# thighPCB.net
KiCad netlist of a schematic drawn in EasyEDA Pro
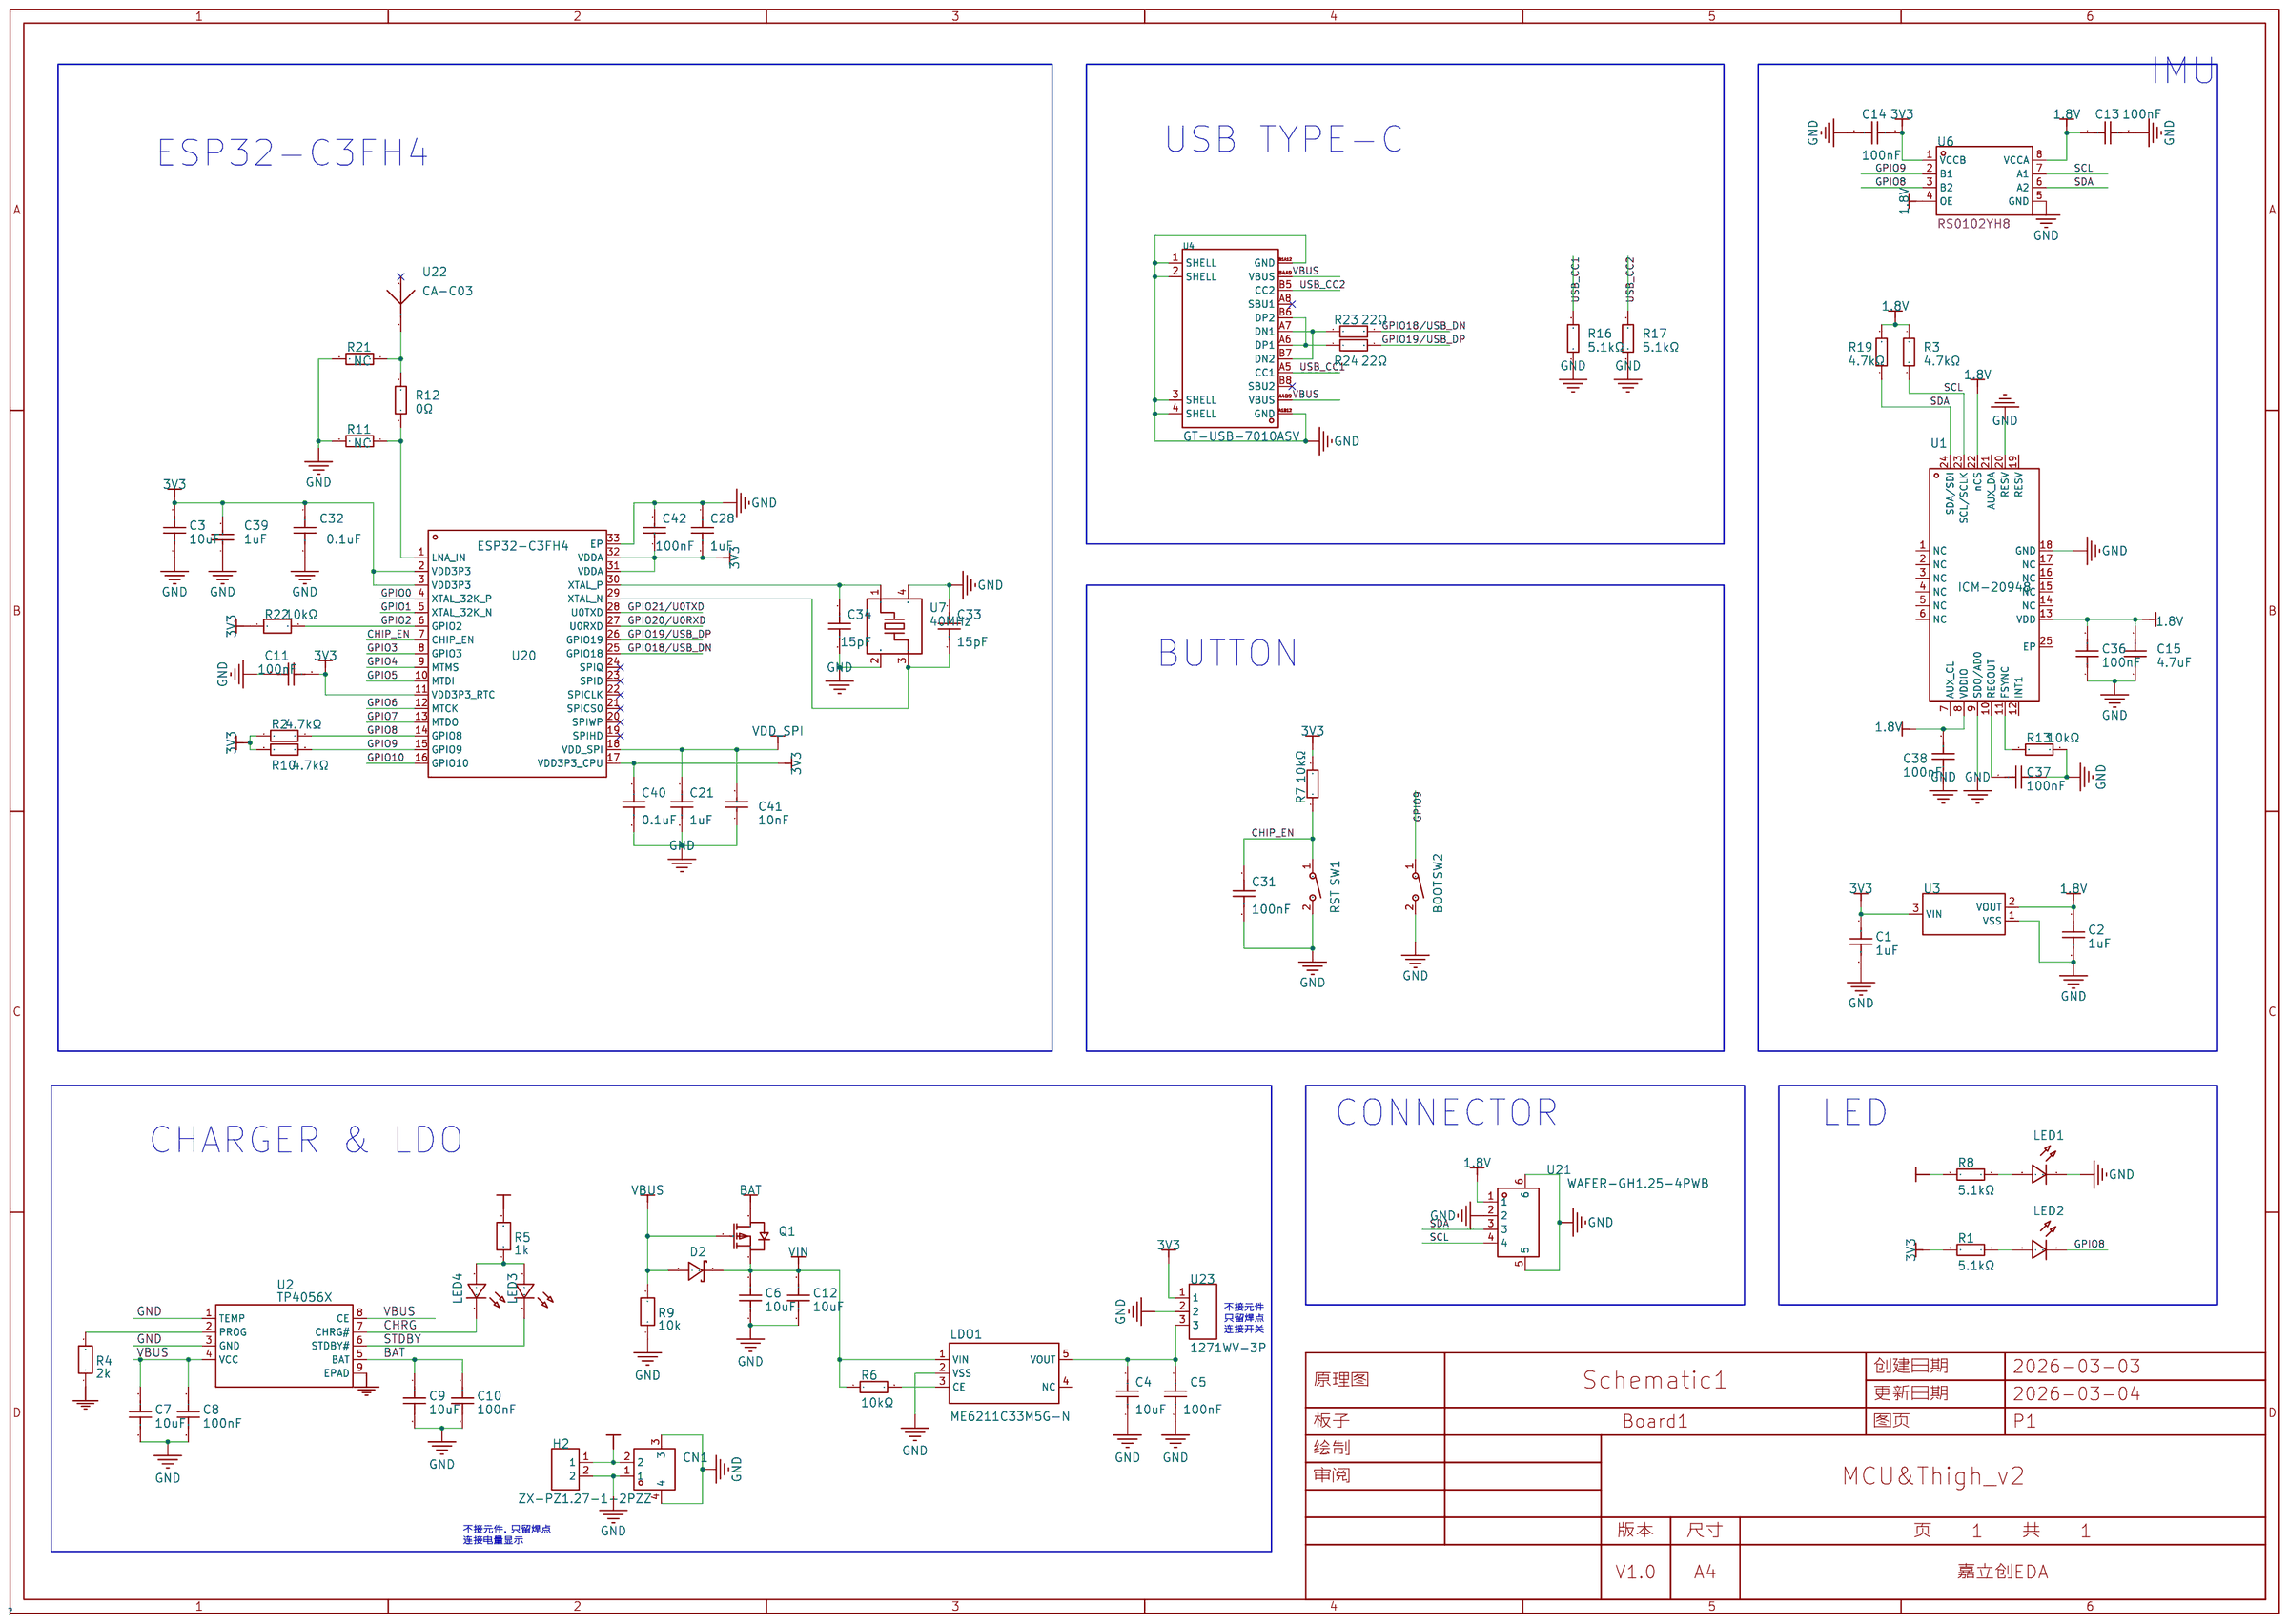
[diagram p0: schematic sheet]

(export (version "E")
  (design (tool "Eeschema 10.0.6"))
  (components
    (comp (ref "C1")
      (value "1uF")
      (footprint "easyedapro:C0603")
      (libsource (lib "easyedapro") (part "Capacitance"))
    )
    (comp (ref "C2")
      (value "1uF")
      (footprint "easyedapro:C0603")
      (libsource (lib "easyedapro") (part "Capacitance"))
    )
    (comp (ref "C3")
      (value "10uF")
      (footprint "easyedapro:C0402")
      (fields
        (field (name "Manufacturer Part") "CL05A106MP5NUNC")
        (field (name "Manufacturer") "SAMSUNG(三星)")
      )
      (libsource (lib "easyedapro") (part "CL05A106MP5NUNC_C315248"))
    )
    (comp (ref "C4")
      (value "10uF")
      (fields
        (field (name "Manufacturer Part") "CL10A106KP8NNNC")
        (field (name "Manufacturer") "SAMSUNG(三星)")
      )
      (libsource (lib "easyedapro") (part "capacitance"))
    )
    (comp (ref "C5")
      (value "100nF")
      (fields
        (field (name "Manufacturer Part") "CGA0603X7R104K500JT")
        (field (name "Manufacturer") "HRE(芯声)")
      )
      (libsource (lib "easyedapro") (part "capacitance"))
    )
    (comp (ref "C6")
      (value "10uF")
      (footprint "easyedapro:C0603")
      (libsource (lib "easyedapro") (part "Capacitance"))
    )
    (comp (ref "C7")
      (value "10uF")
      (footprint "easyedapro:C0603")
      (libsource (lib "easyedapro") (part "Capacitance"))
    )
    (comp (ref "C8")
      (value "100nF")
      (footprint "easyedapro:C0603")
      (libsource (lib "easyedapro") (part "Capacitance"))
    )
    (comp (ref "C9")
      (value "10uF")
      (footprint "easyedapro:C0603")
      (libsource (lib "easyedapro") (part "Capacitance"))
    )
    (comp (ref "C10")
      (value "100nF")
      (footprint "easyedapro:C0603")
      (libsource (lib "easyedapro") (part "Capacitance"))
    )
    (comp (ref "C11")
      (value "100nF")
      (footprint "easyedapro:C0201")
      (fields
        (field (name "Manufacturer Part") "GRM033Z71A104KE14D")
        (field (name "Manufacturer") "muRata(村田)")
      )
      (libsource (lib "easyedapro") (part "GRM033Z71A104KE14D"))
    )
    (comp (ref "C12")
      (value "10uF")
      (footprint "easyedapro:C0603")
      (libsource (lib "easyedapro") (part "Capacitance"))
    )
    (comp (ref "C13")
      (value "100nF")
      (footprint "easyedapro:C0201")
      (description "容值:100nF;精度:±10%;额定电压:10V;材质(温度系数):X7R;")
      (fields
        (field (name "Manufacturer Part") "GRM033Z71A104KE14D")
        (field (name "Manufacturer") "muRata(村田)")
      )
      (libsource (lib "easyedapro") (part "GRM033Z71A104KE14D"))
    )
    (comp (ref "C14")
      (value "100nF")
      (footprint "easyedapro:C0201")
      (description "容值:100nF;精度:±10%;额定电压:10V;材质(温度系数):X7R;")
      (fields
        (field (name "Manufacturer Part") "GRM033Z71A104KE14D")
        (field (name "Manufacturer") "muRata(村田)")
      )
      (libsource (lib "easyedapro") (part "GRM033Z71A104KE14D"))
    )
    (comp (ref "C15")
      (value "4.7uF")
      (footprint "easyedapro:C0603")
      (description "容值:100nF;精度:±10%;额定电压:16V;温度系数:X5R;")
      (fields
        (field (name "Manufacturer Part") "CL03A104KO3NNNC")
        (field (name "Manufacturer") "SAMSUNG(三星)")
      )
      (libsource (lib "easyedapro") (part "Capacitance"))
    )
    (comp (ref "C21")
      (value "1uF")
      (footprint "easyedapro:C0201")
      (fields
        (field (name "Manufacturer Part") "GRM033C81A105ME05D")
        (field (name "Manufacturer") "muRata(村田)")
      )
      (libsource (lib "easyedapro") (part "GRM033C81A105ME05D"))
    )
    (comp (ref "C28")
      (value "1uF")
      (footprint "easyedapro:C0201")
      (fields
        (field (name "Manufacturer Part") "GRM033C81A105ME05D")
        (field (name "Manufacturer") "muRata(村田)")
      )
      (libsource (lib "easyedapro") (part "GRM033C81A105ME05D"))
    )
    (comp (ref "C31")
      (value "100nF")
      (footprint "easyedapro:C0201")
      (fields
        (field (name "Manufacturer Part") "GRM033Z71A104KE14D")
        (field (name "Manufacturer") "muRata(村田)")
      )
      (libsource (lib "easyedapro") (part "GRM033Z71A104KE14D"))
    )
    (comp (ref "C32")
      (value "0.1uF")
      (footprint "easyedapro:C0201")
      (fields
        (field (name "Manufacturer Part") "GRM033Z71A104KE14D")
        (field (name "Manufacturer") "muRata(村田)")
      )
      (libsource (lib "easyedapro") (part "GRM033Z71A104KE14D"))
    )
    (comp (ref "C33")
      (value "15pF")
      (footprint "easyedapro:C0201")
      (fields
        (field (name "Manufacturer Part") "GRM0335C1H150FA01D")
        (field (name "Manufacturer") "muRata(村田)")
      )
      (libsource (lib "easyedapro") (part "GRM0335C1H150FA01D"))
    )
    (comp (ref "C34")
      (value "15pF")
      (footprint "easyedapro:C0201")
      (fields
        (field (name "Manufacturer Part") "GRM0335C1H150FA01D")
        (field (name "Manufacturer") "muRata(村田)")
      )
      (libsource (lib "easyedapro") (part "GRM0335C1H150FA01D"))
    )
    (comp (ref "C36")
      (value "100nF")
      (footprint "easyedapro:C0603")
      (fields
        (field (name "Manufacturer Part") "CL03A104KO3NNNC")
        (field (name "Manufacturer") "SAMSUNG(三星)")
      )
      (libsource (lib "easyedapro") (part "Capacitance"))
    )
    (comp (ref "C37")
      (value "100nF")
      (footprint "easyedapro:C0603")
      (fields
        (field (name "Manufacturer Part") "CL03A104KO3NNNC")
        (field (name "Manufacturer") "SAMSUNG(三星)")
      )
      (libsource (lib "easyedapro") (part "Capacitance"))
    )
    (comp (ref "C38")
      (value "100nF")
      (footprint "easyedapro:C0603")
      (fields
        (field (name "Manufacturer Part") "CL03A104KO3NNNC")
        (field (name "Manufacturer") "SAMSUNG(三星)")
      )
      (libsource (lib "easyedapro") (part "Capacitance"))
    )
    (comp (ref "C39")
      (value "1uF")
      (footprint "easyedapro:C0201")
      (fields
        (field (name "Manufacturer Part") "GRM033R61A105ME44D")
        (field (name "Manufacturer") "muRata(村田)")
      )
      (libsource (lib "easyedapro") (part "GRM033R61A105ME44D"))
    )
    (comp (ref "C40")
      (value "0.1uF")
      (footprint "easyedapro:C0201")
      (fields
        (field (name "Manufacturer Part") "GRM033C81A105ME05D")
        (field (name "Manufacturer") "muRata(村田)")
      )
      (libsource (lib "easyedapro") (part "GRM033C81A105ME05D"))
    )
    (comp (ref "C41")
      (value "10nF")
      (footprint "easyedapro:C0201")
      (fields
        (field (name "Manufacturer Part") "GRM033R71A103KA01D")
        (field (name "Manufacturer") "muRata(村田)")
      )
      (libsource (lib "easyedapro") (part "GRM033R71A103KA01D"))
    )
    (comp (ref "C42")
      (value "100nF")
      (footprint "easyedapro:C0201")
      (fields
        (field (name "Manufacturer Part") "GRM033R61E104KE14D")
        (field (name "Manufacturer") "muRata(村田)")
      )
      (libsource (lib "easyedapro") (part "GRM033R61E104KE14D"))
    )
    (comp (ref "CN1")
      (value "WAFER-GH1.25-2PWB")
      (footprint "easyedapro:CONN-TH_2P-P1.25_XUNPU_WAFER-GH1.25-2PWB")
      (fields (field (name "Manufacturer") "XUNPU(讯普)"))
      (libsource (lib "easyedapro") (part "WAFER-GH1.25-2PWB"))
    )
    (comp (ref "D2")
      (value "1N5819HW-7-F")
      (footprint "easyedapro:SOD-123_L2.7-W1.6-LS3.7-RD")
      (description "二极管配置:1个独立式;正向压降(Vf):450mV@1A;直流反向耐压(Vr):40V;整流电流:1A;")
      (fields (field (name "Manufacturer") "DIODES(美台)"))
      (libsource (lib "easyedapro") (part "1N5819HW-7-F"))
    )
    (comp (ref "H2")
      (value "ZX-PZ1.27-1-2PZZ")
      (footprint "easyedapro:HDR-TH_2P-P1.27-V-M-2")
      (fields (field (name "Manufacturer") "Megastar(兆星)"))
      (libsource (lib "easyedapro") (part "ZX-PZ1.27-1-2PZZ"))
    )
    (comp (ref "LDO1")
      (value "ME6211C33M5G-N")
      (footprint "easyedapro:SOT-23-5_L3.0-W1.7-P0.95-LS2.8-BL")
      (fields (field (name "Manufacturer") "MICRONE(南京微盟)"))
      (libsource (lib "easyedapro") (part "ME6211C33M5G-N"))
    )
    (comp (ref "LED1")
      (value "~")
      (footprint "easyedapro:LED_0402")
      (libsource (lib "easyedapro") (part "LED_R"))
    )
    (comp (ref "LED2")
      (value "~")
      (footprint "easyedapro:LED_0402")
      (libsource (lib "easyedapro") (part "LED_R"))
    )
    (comp (ref "LED3")
      (value "~")
      (footprint "easyedapro:LED_0603")
      (libsource (lib "easyedapro") (part "LED_G"))
    )
    (comp (ref "LED4")
      (value "~")
      (footprint "easyedapro:LED_0402")
      (libsource (lib "easyedapro") (part "LED_R"))
    )
    (comp (ref "Q1")
      (value "HL6042")
      (footprint "easyedapro:SOT-23-3_L2.9-W1.4-P1.90-LS2.5-BR")
      (fields (field (name "Manufacturer") "R+O(宏嘉诚)"))
      (libsource (lib "easyedapro") (part "HL6042"))
    )
    (comp (ref "R1")
      (value "5.1kΩ")
      (footprint "easyedapro:R0201")
      (description "阻值:5.1kΩ;精度:±1%;功率:50mW;")
      (fields (field (name "Manufacturer Part") "RC-01W5101FT") (field (name "Manufacturer") "FH(风华)"))
      (libsource (lib "easyedapro") (part "RC-01W5101FT"))
    )
    (comp (ref "R2")
      (value "4.7kΩ")
      (footprint "easyedapro:R0201")
      (description "电阻类型:厚膜电阻;阻值:10kΩ;精度:±1%;功率:50mW;")
      (fields (field (name "Manufacturer Part") "RC0201FR-0710KL") (field (name "Manufacturer") "YAGEO(国巨)"))
      (libsource (lib "easyedapro") (part "RC0201FR-0710KL"))
    )
    (comp (ref "R3")
      (value "4.7kΩ")
      (footprint "easyedapro:R0201")
      (description "电阻类型:厚膜电阻;阻值:10kΩ;精度:±1%;功率:50mW;")
      (fields (field (name "Manufacturer Part") "RC0201FR-0710KL") (field (name "Manufacturer") "YAGEO(国巨)"))
      (libsource (lib "easyedapro") (part "RC0201FR-0710KL"))
    )
    (comp (ref "R4")
      (value "2k")
      (footprint "easyedapro:R0603")
      (fields (field (name "Contributor") "LCEDA_Lib"))
      (libsource (lib "easyedapro") (part "2k"))
    )
    (comp (ref "R5")
      (value "1k")
      (footprint "easyedapro:R0603")
      (fields (field (name "Contributor") "LCEDA_Lib"))
      (libsource (lib "easyedapro") (part "1k"))
    )
    (comp (ref "R6")
      (value "10kΩ")
      (fields (field (name "Manufacturer Part") "FRC0603J103TS") (field (name "Manufacturer") "FOJAN(富捷)"))
      (libsource (lib "easyedapro") (part "电阻"))
    )
    (comp (ref "R7")
      (value "10kΩ")
      (footprint "easyedapro:R0201")
      (fields (field (name "Manufacturer Part") "RC0201FR-0710KL") (field (name "Manufacturer") "YAGEO(国巨)"))
      (libsource (lib "easyedapro") (part "RC0201FR-0710KL"))
    )
    (comp (ref "R8")
      (value "5.1kΩ")
      (footprint "easyedapro:R0201")
      (fields (field (name "Manufacturer Part") "RC-01W5101FT") (field (name "Manufacturer") "FH(风华)"))
      (libsource (lib "easyedapro") (part "RC-01W5101FT"))
    )
    (comp (ref "R9")
      (value "10k")
      (footprint "easyedapro:R0603")
      (fields (field (name "Contributor") "LCEDA_Lib"))
      (libsource (lib "easyedapro") (part "1k"))
    )
    (comp (ref "R10")
      (value "4.7kΩ")
      (footprint "easyedapro:R0201")
      (description "电阻类型:厚膜电阻;阻值:10kΩ;精度:±1%;功率:50mW;")
      (fields (field (name "Manufacturer Part") "RC0201FR-0710KL") (field (name "Manufacturer") "YAGEO(国巨)"))
      (libsource (lib "easyedapro") (part "RC0201FR-0710KL"))
    )
    (comp (ref "R11")
      (value "NC")
      (footprint "easyedapro:R0201")
      (fields (field (name "Manufacturer Part") "RC0201JR-070RL") (field (name "Manufacturer") "YAGEO(国巨)"))
      (libsource (lib "easyedapro") (part "RC0201JR-070RL"))
    )
    (comp (ref "R12")
      (value "0Ω")
      (footprint "easyedapro:R0201")
      (fields (field (name "Manufacturer Part") "RC0201JR-070RL") (field (name "Manufacturer") "YAGEO(国巨)"))
      (libsource (lib "easyedapro") (part "RC0201JR-070RL"))
    )
    (comp (ref "R13")
      (value "10kΩ")
      (footprint "easyedapro:R0201")
      (description "电阻类型:厚膜电阻;阻值:10kΩ;精度:±1%;功率:50mW;")
      (fields (field (name "Manufacturer Part") "RC0201FR-0710KL") (field (name "Manufacturer") "YAGEO(国巨)"))
      (libsource (lib "easyedapro") (part "RC0201FR-0710KL"))
    )
    (comp (ref "R16")
      (value "5.1kΩ")
      (footprint "easyedapro:R0201")
      (fields (field (name "Manufacturer Part") "RC-01W5101FT") (field (name "Manufacturer") "FH(风华)"))
      (libsource (lib "easyedapro") (part "RC-01W5101FT"))
    )
    (comp (ref "R17")
      (value "5.1kΩ")
      (footprint "easyedapro:R0201")
      (fields (field (name "Manufacturer Part") "RC-01W5101FT") (field (name "Manufacturer") "FH(风华)"))
      (libsource (lib "easyedapro") (part "RC-01W5101FT"))
    )
    (comp (ref "R19")
      (value "4.7kΩ")
      (footprint "easyedapro:R0201")
      (description "电阻类型:厚膜电阻;阻值:10kΩ;精度:±1%;功率:50mW;")
      (fields (field (name "Manufacturer Part") "RC0201FR-0710KL") (field (name "Manufacturer") "YAGEO(国巨)"))
      (libsource (lib "easyedapro") (part "RC0201FR-0710KL"))
    )
    (comp (ref "R21")
      (value "NC")
      (footprint "easyedapro:R0201")
      (fields (field (name "Manufacturer Part") "RC0201JR-070RL") (field (name "Manufacturer") "YAGEO(国巨)"))
      (libsource (lib "easyedapro") (part "RC0201JR-070RL"))
    )
    (comp (ref "R22")
      (value "10kΩ")
      (footprint "easyedapro:R0201")
      (fields (field (name "Manufacturer Part") "FRC0201J103 TS") (field (name "Manufacturer") "FOJAN(富捷)"))
      (libsource (lib "easyedapro") (part "FRC0201J103 TS"))
    )
    (comp (ref "R23")
      (value "22Ω")
      (footprint "easyedapro:R0201")
      (fields (field (name "Manufacturer Part") "RC0201FR-0722RL") (field (name "Manufacturer") "YAGEO(国巨)"))
      (libsource (lib "easyedapro") (part "RC0201FR-0722RL"))
    )
    (comp (ref "R24")
      (value "22Ω")
      (footprint "easyedapro:R0201")
      (fields (field (name "Manufacturer Part") "RC0201FR-0722RL") (field (name "Manufacturer") "YAGEO(国巨)"))
      (libsource (lib "easyedapro") (part "RC0201FR-0722RL"))
    )
    (comp (ref "SW1")
      (value "RST")
      (footprint "easyedapro:SW-SMD_L4.0-W2.9-LS5.0")
      (fields
        (field (name "Manufacturer Part") "TS-1185-C-B-B-A")
        (field (name "Manufacturer") "XKB Connectivity(中国星坤)")
      )
      (libsource (lib "easyedapro") (part "TS-1185-C-B-B-A"))
    )
    (comp (ref "SW2")
      (value "BOOT")
      (footprint "easyedapro:SW-SMD_L4.0-W2.9-LS5.0")
      (fields
        (field (name "Manufacturer Part") "TS-1185-C-B-B-A")
        (field (name "Manufacturer") "XKB Connectivity(中国星坤)")
      )
      (libsource (lib "easyedapro") (part "TS-1185-C-B-B-A"))
    )
    (comp (ref "U1")
      (value "ICM-20948")
      (footprint "easyedapro:QFN-24_L3.0-W3.0-P0.40-BL-EP")
      (fields (field (name "Manufacturer") "TDK InvenSense(应美盛)"))
      (libsource (lib "easyedapro") (part "ICM-20948"))
    )
    (comp (ref "U2")
      (value "TP4056X")
      (footprint "easyedapro:SOP-8_L4.9-W3.9-P1.27-LS6.0-BL-EP")
      (fields
        (field (name "Manufacturer") "Nanjing Extension Microelectronics")
        (field (name "Contributor") "LCSC")
      )
      (libsource (lib "easyedapro") (part "TP4056X"))
    )
    (comp (ref "U3")
      (value "ME6211A18M3G-N")
      (footprint "easyedapro:SOT-23-3_L3.0-W1.7-P0.95-LS2.9-BR")
      (fields (field (name "Manufacturer") "MICRONE(南京微盟)"))
      (libsource (lib "easyedapro") (part "ME6211A18M3G-N"))
    )
    (comp (ref "U4")
      (value "GT-USB-7010ASV")
      (footprint "easyedapro:USB-C-SMD_G-SWITCH_GT-USB-7010ASV")
      (fields (field (name "Manufacturer") "G-Switch(品赞)"))
      (libsource (lib "easyedapro") (part "GT-USB-7010ASV"))
    )
    (comp (ref "U6")
      (value "RS0102YH8")
      (footprint "easyedapro:SOT-23-8_L3.0-W1.7-P0.65-LS2.8-BL")
      (fields (field (name "Manufacturer Part") "RS0102YH8") (field (name "Manufacturer") "RUNIC(润石)"))
      (libsource (lib "easyedapro") (part "RS0102YH8"))
    )
    (comp (ref "U7")
      (value "40MHz")
      (footprint "easyedapro:CRYSTAL-SMD_4P-L2.0-W1.6-BL")
      (fields (field (name "Manufacturer Part") "TAXM40M4ZHBCDT2T") (field (name "Manufacturer") "YJX(雅晶鑫)"))
      (libsource (lib "easyedapro") (part "TAXM40M4ZHBCDT2T"))
    )
    (comp (ref "U20")
      (value "ESP32-C3FH4")
      (fields (field (name "Manufacturer") "ESPRESSIF(乐鑫)"))
      (libsource (lib "easyedapro") (part "ESP32-C3FH4"))
    )
    (comp (ref "U21")
      (value "WAFER-GH1.25-4PWB")
      (footprint "easyedapro:CONN-SMD_4P-P1.25_XUNPU_WAFER-GH1.25-4PWB")
      (fields (field (name "Manufacturer") "XUNPU(讯普)"))
      (libsource (lib "easyedapro") (part "WAFER-GH1.25-4PWB"))
    )
    (comp (ref "U22")
      (value "CA-C03")
      (footprint "easyedapro:ANT-SMD_CA-C03")
      (libsource (lib "easyedapro") (part "CA-C03_C9900042552"))
    )
    (comp (ref "U23")
      (value "1271WV-3P")
      (footprint "easyedapro:HDR-TH_3P-P1.27-V-M")
      (fields (field (name "Manufacturer") "HanElectricity(瀚源)"))
      (libsource (lib "easyedapro") (part "1271WV-3P"))
    )
  )
  (nets
    (net (code "1") (name "/CHIP_EN") (class "Default")
      (node (ref "C31") (pin "1") (pinfunction "1_1") (pintype "input"))
      (node (ref "R7") (pin "1") (pinfunction "1_1") (pintype "input"))
      (node (ref "SW1") (pin "1") (pinfunction "1_1") (pintype "input"))
      (node (ref "U20") (pin "7") (pinfunction "CHIP_EN_7") (pintype "input"))
    )
    (net (code "2") (name "/CHRG") (class "Default")
      (node (ref "LED4") (pin "1") (pinfunction "C_1") (pintype "input"))
      (node (ref "U2") (pin "7") (pinfunction "CHRG#_7") (pintype "unspecified"))
    )
    (net (code "3") (name "/GPIO0") (class "Default")
      (node (ref "U20") (pin "4") (pinfunction "XTAL_32K_P_4") (pintype "input"))
    )
    (net (code "4") (name "/GPIO1") (class "Default")
      (node (ref "U20") (pin "5") (pinfunction "XTAL_32K_N_5") (pintype "input"))
    )
    (net (code "5") (name "/GPIO2") (class "Default")
      (node (ref "R22") (pin "2") (pinfunction "2_2") (pintype "unspecified"))
      (node (ref "U20") (pin "6") (pinfunction "GPIO2_6") (pintype "input"))
    )
    (net (code "6") (name "/GPIO3") (class "Default")
      (node (ref "U20") (pin "8") (pinfunction "GPIO3_8") (pintype "input"))
    )
    (net (code "7") (name "/GPIO4") (class "Default")
      (node (ref "U20") (pin "9") (pinfunction "MTMS_9") (pintype "input"))
    )
    (net (code "8") (name "/GPIO5") (class "Default")
      (node (ref "U20") (pin "10") (pinfunction "MTDI_10") (pintype "input"))
    )
    (net (code "9") (name "/GPIO6") (class "Default")
      (node (ref "U20") (pin "12") (pinfunction "MTCK_12") (pintype "input"))
    )
    (net (code "10") (name "/GPIO7") (class "Default")
      (node (ref "U20") (pin "13") (pinfunction "MTDO_13") (pintype "input"))
    )
    (net (code "11") (name "/GPIO8") (class "Default")
      (node (ref "LED2") (pin "1") (pinfunction "C_1") (pintype "input"))
      (node (ref "R2") (pin "2") (pinfunction "2_2") (pintype "input"))
      (node (ref "U20") (pin "14") (pinfunction "GPIO8_14") (pintype "input"))
      (node (ref "U6") (pin "3") (pinfunction "B2_3") (pintype "unspecified"))
    )
    (net (code "12") (name "/GPIO9") (class "Default")
      (node (ref "R10") (pin "2") (pinfunction "2_2") (pintype "input"))
      (node (ref "SW2") (pin "1") (pinfunction "1_1") (pintype "input"))
      (node (ref "U20") (pin "15") (pinfunction "GPIO9_15") (pintype "input"))
      (node (ref "U6") (pin "2") (pinfunction "B1_2") (pintype "unspecified"))
    )
    (net (code "13") (name "/GPIO10") (class "Default")
      (node (ref "U20") (pin "16") (pinfunction "GPIO10_16") (pintype "input"))
    )
    (net (code "14") (name "/GPIO18{slash}USB_DN") (class "Default")
      (node (ref "R23") (pin "2") (pinfunction "2_2") (pintype "unspecified"))
      (node (ref "U20") (pin "25") (pinfunction "GPIO18_25") (pintype "input"))
    )
    (net (code "15") (name "/GPIO19{slash}USB_DP") (class "Default")
      (node (ref "R24") (pin "2") (pinfunction "2_2") (pintype "unspecified"))
      (node (ref "U20") (pin "26") (pinfunction "GPIO19_26") (pintype "input"))
    )
    (net (code "16") (name "/GPIO20{slash}U0RXD") (class "Default")
      (node (ref "U20") (pin "27") (pinfunction "U0RXD_27") (pintype "input"))
    )
    (net (code "17") (name "/GPIO21{slash}U0TXD") (class "Default")
      (node (ref "U20") (pin "28") (pinfunction "U0TXD_28") (pintype "input"))
    )
    (net (code "18") (name "/SCL") (class "Default")
      (node (ref "R3") (pin "2") (pinfunction "2_2") (pintype "input"))
      (node (ref "U1") (pin "23") (pinfunction "SCL/SCLK_23") (pintype "unspecified"))
      (node (ref "U21") (pin "4") (pinfunction "4_4") (pintype "unspecified"))
      (node (ref "U6") (pin "7") (pinfunction "A1_7") (pintype "unspecified"))
    )
    (net (code "19") (name "/SDA") (class "Default")
      (node (ref "R19") (pin "1") (pinfunction "1_1") (pintype "input"))
      (node (ref "U1") (pin "24") (pinfunction "SDA/SDI_24") (pintype "unspecified"))
      (node (ref "U21") (pin "3") (pinfunction "3_3") (pintype "unspecified"))
      (node (ref "U6") (pin "6") (pinfunction "A2_6") (pintype "unspecified"))
    )
    (net (code "20") (name "/STDBY") (class "Default")
      (node (ref "LED3") (pin "1") (pinfunction "C_1") (pintype "input"))
      (node (ref "U2") (pin "6") (pinfunction "STDBY#_6") (pintype "unspecified"))
    )
    (net (code "21") (name "/USB_CC1") (class "Default")
      (node (ref "R16") (pin "2") (pinfunction "2_2") (pintype "input"))
      (node (ref "U4") (pin "A5") (pinfunction "CC1_A5") (pintype "input"))
    )
    (net (code "22") (name "/USB_CC2") (class "Default")
      (node (ref "R17") (pin "2") (pinfunction "2_2") (pintype "input"))
      (node (ref "U4") (pin "B5") (pinfunction "CC2_B5") (pintype "input"))
    )
    (net (code "23") (name "1.8V") (class "Default")
      (node (ref "C13") (pin "1") (pinfunction "1_1") (pintype "input"))
      (node (ref "C15") (pin "2") (pinfunction "2_2") (pintype "input"))
      (node (ref "C2") (pin "1") (pinfunction "1_1") (pintype "input"))
      (node (ref "C36") (pin "2") (pinfunction "2_2") (pintype "input"))
      (node (ref "C38") (pin "2") (pinfunction "2_2") (pintype "input"))
      (node (ref "R19") (pin "2") (pinfunction "2_2") (pintype "input"))
      (node (ref "R3") (pin "1") (pinfunction "1_1") (pintype "input"))
      (node (ref "U1") (pin "13") (pinfunction "VDD_13") (pintype "unspecified"))
      (node (ref "U1") (pin "22") (pinfunction "nCS_22") (pintype "unspecified"))
      (node (ref "U1") (pin "8") (pinfunction "VDDIO_8") (pintype "unspecified"))
      (node (ref "U21") (pin "1") (pinfunction "1_1") (pintype "unspecified"))
      (node (ref "U3") (pin "2") (pinfunction "VOUT_2") (pintype "unspecified"))
      (node (ref "U6") (pin "4") (pinfunction "OE_4") (pintype "unspecified"))
      (node (ref "U6") (pin "8") (pinfunction "VCCA_8") (pintype "unspecified"))
    )
    (net (code "24") (name "3V3") (class "Default")
      (node (ref "C1") (pin "1") (pinfunction "1_1") (pintype "input"))
      (node (ref "C11") (pin "2") (pinfunction "2_2") (pintype "input"))
      (node (ref "C14") (pin "1") (pinfunction "1_1") (pintype "input"))
      (node (ref "C28") (pin "2") (pinfunction "2_2") (pintype "input"))
      (node (ref "C3") (pin "2") (pinfunction "2_2") (pintype "unspecified"))
      (node (ref "C32") (pin "1") (pinfunction "1_1") (pintype "input"))
      (node (ref "C39") (pin "2") (pinfunction "2_2") (pintype "input"))
      (node (ref "C40") (pin "1") (pinfunction "1_1") (pintype "input"))
      (node (ref "C42") (pin "2") (pinfunction "2_2") (pintype "input"))
      (node (ref "R1") (pin "2") (pinfunction "2_2") (pintype "input"))
      (node (ref "R10") (pin "1") (pinfunction "1_1") (pintype "input"))
      (node (ref "R2") (pin "1") (pinfunction "1_1") (pintype "input"))
      (node (ref "R22") (pin "1") (pinfunction "1_1") (pintype "unspecified"))
      (node (ref "R7") (pin "2") (pinfunction "2_2") (pintype "input"))
      (node (ref "U20") (pin "11") (pinfunction "VDD3P3_RTC_11") (pintype "input"))
      (node (ref "U20") (pin "17") (pinfunction "VDD3P3_CPU_17") (pintype "input"))
      (node (ref "U20") (pin "2") (pinfunction "VDD3P3_2") (pintype "input"))
      (node (ref "U20") (pin "3") (pinfunction "VDD3P3_3") (pintype "input"))
      (node (ref "U20") (pin "31") (pinfunction "VDDA_31") (pintype "input"))
      (node (ref "U20") (pin "32") (pinfunction "VDDA_32") (pintype "input"))
      (node (ref "U23") (pin "1") (pinfunction "1_1") (pintype "unspecified"))
      (node (ref "U3") (pin "3") (pinfunction "VIN_3") (pintype "unspecified"))
      (node (ref "U6") (pin "1") (pinfunction "VCCB_1") (pintype "unspecified"))
    )
    (net (code "25") (name "BAT") (class "Default")
      (node (ref "C10") (pin "1") (pinfunction "1_1") (pintype "input"))
      (node (ref "C9") (pin "1") (pinfunction "1_1") (pintype "input"))
      (node (ref "CN1") (pin "2") (pinfunction "2_2") (pintype "unspecified"))
      (node (ref "H2") (pin "1") (pinfunction "1_1") (pintype "unspecified"))
      (node (ref "Q1") (pin "3") (pinfunction "D_3") (pintype "unspecified"))
      (node (ref "U2") (pin "5") (pinfunction "BAT_5") (pintype "unspecified"))
    )
    (net (code "26") (name "GND") (class "Default")
      (node (ref "C1") (pin "2") (pinfunction "2_2") (pintype "input"))
      (node (ref "C10") (pin "2") (pinfunction "2_2") (pintype "input"))
      (node (ref "C11") (pin "1") (pinfunction "1_1") (pintype "input"))
      (node (ref "C12") (pin "1") (pinfunction "1_1") (pintype "input"))
      (node (ref "C13") (pin "2") (pinfunction "2_2") (pintype "input"))
      (node (ref "C14") (pin "2") (pinfunction "2_2") (pintype "input"))
      (node (ref "C15") (pin "1") (pinfunction "1_1") (pintype "input"))
      (node (ref "C2") (pin "2") (pinfunction "2_2") (pintype "input"))
      (node (ref "C21") (pin "2") (pinfunction "2_2") (pintype "input"))
      (node (ref "C28") (pin "1") (pinfunction "1_1") (pintype "input"))
      (node (ref "C3") (pin "1") (pinfunction "1_1") (pintype "unspecified"))
      (node (ref "C31") (pin "2") (pinfunction "2_2") (pintype "input"))
      (node (ref "C32") (pin "2") (pinfunction "2_2") (pintype "input"))
      (node (ref "C33") (pin "1") (pinfunction "1_1") (pintype "input"))
      (node (ref "C34") (pin "2") (pinfunction "2_2") (pintype "input"))
      (node (ref "C36") (pin "1") (pinfunction "1_1") (pintype "input"))
      (node (ref "C37") (pin "1") (pinfunction "1_1") (pintype "input"))
      (node (ref "C38") (pin "1") (pinfunction "1_1") (pintype "input"))
      (node (ref "C39") (pin "1") (pinfunction "1_1") (pintype "input"))
      (node (ref "C4") (pin "1") (pinfunction "1_1") (pintype "input"))
      (node (ref "C40") (pin "2") (pinfunction "2_2") (pintype "input"))
      (node (ref "C41") (pin "1") (pinfunction "1_1") (pintype "input"))
      (node (ref "C42") (pin "1") (pinfunction "1_1") (pintype "input"))
      (node (ref "C5") (pin "1") (pinfunction "1_1") (pintype "input"))
      (node (ref "C6") (pin "1") (pinfunction "1_1") (pintype "input"))
      (node (ref "C7") (pin "2") (pinfunction "2_2") (pintype "input"))
      (node (ref "C8") (pin "2") (pinfunction "2_2") (pintype "input"))
      (node (ref "C9") (pin "2") (pinfunction "2_2") (pintype "input"))
      (node (ref "CN1") (pin "1") (pinfunction "1_1") (pintype "unspecified"))
      (node (ref "CN1") (pin "3") (pinfunction "3_3") (pintype "unspecified"))
      (node (ref "CN1") (pin "4") (pinfunction "4_4") (pintype "unspecified"))
      (node (ref "H2") (pin "2") (pinfunction "2_2") (pintype "unspecified"))
      (node (ref "LDO1") (pin "2") (pinfunction "VSS_2") (pintype "unspecified"))
      (node (ref "LED1") (pin "1") (pinfunction "C_1") (pintype "input"))
      (node (ref "R11") (pin "2") (pinfunction "2_2") (pintype "input"))
      (node (ref "R13") (pin "2") (pinfunction "2_2") (pintype "input"))
      (node (ref "R16") (pin "1") (pinfunction "1_1") (pintype "input"))
      (node (ref "R17") (pin "1") (pinfunction "1_1") (pintype "input"))
      (node (ref "R21") (pin "2") (pinfunction "2_2") (pintype "input"))
      (node (ref "R4") (pin "1") (pinfunction "1_1") (pintype "unspecified"))
      (node (ref "R9") (pin "1") (pinfunction "1_1") (pintype "unspecified"))
      (node (ref "SW1") (pin "2") (pinfunction "2_2") (pintype "input"))
      (node (ref "SW2") (pin "2") (pinfunction "2_2") (pintype "input"))
      (node (ref "U1") (pin "18") (pinfunction "GND_18") (pintype "unspecified"))
      (node (ref "U1") (pin "20") (pinfunction "RESV_20") (pintype "unspecified"))
      (node (ref "U1") (pin "9") (pinfunction "SDO/AD0_9") (pintype "unspecified"))
      (node (ref "U2") (pin "1") (pinfunction "TEMP_1") (pintype "unspecified"))
      (node (ref "U2") (pin "3") (pinfunction "GND_3") (pintype "unspecified"))
      (node (ref "U2") (pin "9") (pinfunction "EPAD_9") (pintype "unspecified"))
      (node (ref "U20") (pin "33") (pinfunction "EP_33") (pintype "input"))
      (node (ref "U21") (pin "2") (pinfunction "2_2") (pintype "unspecified"))
      (node (ref "U21") (pin "5") (pinfunction "5_5") (pintype "unspecified"))
      (node (ref "U21") (pin "6") (pinfunction "6_6") (pintype "unspecified"))
      (node (ref "U23") (pin "2") (pinfunction "2_2") (pintype "unspecified"))
      (node (ref "U3") (pin "1") (pinfunction "VSS_1") (pintype "unspecified"))
      (node (ref "U4") (pin "1") (pinfunction "SHELL_1") (pintype "input"))
      (node (ref "U4") (pin "2") (pinfunction "SHELL_2") (pintype "input"))
      (node (ref "U4") (pin "3") (pinfunction "SHELL_3") (pintype "input"))
      (node (ref "U4") (pin "4") (pinfunction "SHELL_4") (pintype "input"))
      (node (ref "U4") (pin "A1B12") (pinfunction "GND_A1B12") (pintype "input"))
      (node (ref "U4") (pin "B1A12") (pinfunction "GND_B1A12") (pintype "input"))
      (node (ref "U6") (pin "5") (pinfunction "GND_5") (pintype "unspecified"))
      (node (ref "U7") (pin "2") (pinfunction "GND_2") (pintype "input"))
      (node (ref "U7") (pin "4") (pinfunction "GND_4") (pintype "input"))
    )
    (net (code "27") (name "Net-(LDO1-CE)") (class "Default")
      (node (ref "LDO1") (pin "3") (pinfunction "CE_3") (pintype "unspecified"))
      (node (ref "R6") (pin "2") (pinfunction "2_2") (pintype "input"))
    )
    (net (code "28") (name "Net-(LDO1-VOUT)") (class "Default")
      (node (ref "C4") (pin "2") (pinfunction "2_2") (pintype "input"))
      (node (ref "C5") (pin "2") (pinfunction "2_2") (pintype "input"))
      (node (ref "LDO1") (pin "5") (pinfunction "VOUT_5") (pintype "unspecified"))
      (node (ref "U23") (pin "3") (pinfunction "3_3") (pintype "unspecified"))
    )
    (net (code "29") (name "Net-(LED1-A)") (class "Default")
      (node (ref "LED1") (pin "2") (pinfunction "A_2") (pintype "input"))
      (node (ref "R8") (pin "1") (pinfunction "1_1") (pintype "input"))
    )
    (net (code "30") (name "Net-(LED2-A)") (class "Default")
      (node (ref "LED2") (pin "2") (pinfunction "A_2") (pintype "input"))
      (node (ref "R1") (pin "1") (pinfunction "1_1") (pintype "input"))
    )
    (net (code "31") (name "Net-(LED3-A)") (class "Default")
      (node (ref "LED3") (pin "2") (pinfunction "A_2") (pintype "input"))
      (node (ref "LED4") (pin "2") (pinfunction "A_2") (pintype "input"))
      (node (ref "R5") (pin "1") (pinfunction "1_1") (pintype "unspecified"))
    )
    (net (code "32") (name "Net-(R12-Pad2)") (class "Default")
      (node (ref "R12") (pin "2") (pinfunction "2_2") (pintype "input"))
      (node (ref "R21") (pin "1") (pinfunction "1_1") (pintype "input"))
      (node (ref "U22") (pin "1") (pinfunction "1_1") (pintype "unspecified"))
    )
    (net (code "33") (name "Net-(U1-FSYNC)") (class "Default")
      (node (ref "R13") (pin "1") (pinfunction "1_1") (pintype "input"))
      (node (ref "U1") (pin "11") (pinfunction "FSYNC_11") (pintype "unspecified"))
    )
    (net (code "34") (name "Net-(U1-REGOUT)") (class "Default")
      (node (ref "C37") (pin "2") (pinfunction "2_2") (pintype "input"))
      (node (ref "U1") (pin "10") (pinfunction "REGOUT_10") (pintype "unspecified"))
    )
    (net (code "35") (name "Net-(U2-PROG)") (class "Default")
      (node (ref "R4") (pin "2") (pinfunction "2_2") (pintype "unspecified"))
      (node (ref "U2") (pin "2") (pinfunction "PROG_2") (pintype "unspecified"))
    )
    (net (code "36") (name "Net-(U4-DN1)") (class "Default")
      (node (ref "R23") (pin "1") (pinfunction "1_1") (pintype "unspecified"))
      (node (ref "U4") (pin "A7") (pinfunction "DN1_A7") (pintype "input"))
      (node (ref "U4") (pin "B7") (pinfunction "DN2_B7") (pintype "input"))
    )
    (net (code "37") (name "Net-(U4-DP1)") (class "Default")
      (node (ref "R24") (pin "1") (pinfunction "1_1") (pintype "unspecified"))
      (node (ref "U4") (pin "A6") (pinfunction "DP1_A6") (pintype "input"))
      (node (ref "U4") (pin "B6") (pinfunction "DP2_B6") (pintype "input"))
    )
    (net (code "38") (name "Net-(U20-LNA_IN)") (class "Default")
      (node (ref "R11") (pin "1") (pinfunction "1_1") (pintype "input"))
      (node (ref "R12") (pin "1") (pinfunction "1_1") (pintype "input"))
      (node (ref "U20") (pin "1") (pinfunction "LNA_IN_1") (pintype "input"))
    )
    (net (code "39") (name "Net-(U20-XTAL_N)") (class "Default")
      (node (ref "C33") (pin "2") (pinfunction "2_2") (pintype "input"))
      (node (ref "U20") (pin "29") (pinfunction "XTAL_N_29") (pintype "input"))
      (node (ref "U7") (pin "3") (pinfunction "3_3") (pintype "input"))
    )
    (net (code "40") (name "Net-(U20-XTAL_P)") (class "Default")
      (node (ref "C34") (pin "1") (pinfunction "1_1") (pintype "input"))
      (node (ref "U20") (pin "30") (pinfunction "XTAL_P_30") (pintype "input"))
      (node (ref "U7") (pin "1") (pinfunction "1_1") (pintype "input"))
    )
    (net (code "41") (name "VBUS") (class "Default")
      (node (ref "C7") (pin "1") (pinfunction "1_1") (pintype "input"))
      (node (ref "C8") (pin "1") (pinfunction "1_1") (pintype "input"))
      (node (ref "D2") (pin "2") (pinfunction "A_2") (pintype "unspecified"))
      (node (ref "Q1") (pin "1") (pinfunction "G_1") (pintype "unspecified"))
      (node (ref "R5") (pin "2") (pinfunction "2_2") (pintype "unspecified"))
      (node (ref "R8") (pin "2") (pinfunction "2_2") (pintype "input"))
      (node (ref "R9") (pin "2") (pinfunction "2_2") (pintype "unspecified"))
      (node (ref "U2") (pin "4") (pinfunction "VCC_4") (pintype "unspecified"))
      (node (ref "U2") (pin "8") (pinfunction "CE_8") (pintype "unspecified"))
      (node (ref "U4") (pin "A4B9") (pinfunction "VBUS_A4B9") (pintype "input"))
      (node (ref "U4") (pin "B4A9") (pinfunction "VBUS_B4A9") (pintype "input"))
    )
    (net (code "42") (name "VDD_SPI") (class "Default")
      (node (ref "C21") (pin "1") (pinfunction "1_1") (pintype "input"))
      (node (ref "C41") (pin "2") (pinfunction "2_2") (pintype "input"))
      (node (ref "U20") (pin "18") (pinfunction "VDD_SPI_18") (pintype "input"))
    )
    (net (code "43") (name "VIN") (class "Default")
      (node (ref "C12") (pin "2") (pinfunction "2_2") (pintype "input"))
      (node (ref "C6") (pin "2") (pinfunction "2_2") (pintype "input"))
      (node (ref "D2") (pin "1") (pinfunction "K_1") (pintype "unspecified"))
      (node (ref "LDO1") (pin "1") (pinfunction "VIN_1") (pintype "unspecified"))
      (node (ref "Q1") (pin "2") (pinfunction "S_2") (pintype "unspecified"))
      (node (ref "R6") (pin "1") (pinfunction "1_1") (pintype "input"))
    )
    (net (code "44") (name "unconnected-(LDO1-NC-Pad4)") (class "Default")
      (node (ref "LDO1") (pin "4") (pinfunction "NC_4") (pintype "unspecified"))
    )
    (net (code "45") (name "unconnected-(U1-AUX_CL-Pad7)") (class "Default")
      (node (ref "U1") (pin "7") (pinfunction "AUX_CL_7") (pintype "unspecified"))
    )
    (net (code "46") (name "unconnected-(U1-AUX_DA-Pad21)") (class "Default")
      (node (ref "U1") (pin "21") (pinfunction "AUX_DA_21") (pintype "unspecified"))
    )
    (net (code "47") (name "unconnected-(U1-EP-Pad25)") (class "Default")
      (node (ref "U1") (pin "25") (pinfunction "EP_25") (pintype "unspecified"))
    )
    (net (code "48") (name "unconnected-(U1-INT1-Pad12)") (class "Default")
      (node (ref "U1") (pin "12") (pinfunction "INT1_12") (pintype "unspecified"))
    )
    (net (code "49") (name "unconnected-(U1-NC-Pad1)") (class "Default")
      (node (ref "U1") (pin "1") (pinfunction "NC_1") (pintype "unspecified"))
    )
    (net (code "50") (name "unconnected-(U1-NC-Pad2)") (class "Default")
      (node (ref "U1") (pin "2") (pinfunction "NC_2") (pintype "unspecified"))
    )
    (net (code "51") (name "unconnected-(U1-NC-Pad3)") (class "Default")
      (node (ref "U1") (pin "3") (pinfunction "NC_3") (pintype "unspecified"))
    )
    (net (code "52") (name "unconnected-(U1-NC-Pad4)") (class "Default")
      (node (ref "U1") (pin "4") (pinfunction "NC_4") (pintype "unspecified"))
    )
    (net (code "53") (name "unconnected-(U1-NC-Pad5)") (class "Default")
      (node (ref "U1") (pin "5") (pinfunction "NC_5") (pintype "unspecified"))
    )
    (net (code "54") (name "unconnected-(U1-NC-Pad6)") (class "Default")
      (node (ref "U1") (pin "6") (pinfunction "NC_6") (pintype "unspecified"))
    )
    (net (code "55") (name "unconnected-(U1-NC-Pad14)") (class "Default")
      (node (ref "U1") (pin "14") (pinfunction "NC_14") (pintype "unspecified"))
    )
    (net (code "56") (name "unconnected-(U1-NC-Pad15)") (class "Default")
      (node (ref "U1") (pin "15") (pinfunction "NC_15") (pintype "unspecified"))
    )
    (net (code "57") (name "unconnected-(U1-NC-Pad16)") (class "Default")
      (node (ref "U1") (pin "16") (pinfunction "NC_16") (pintype "unspecified"))
    )
    (net (code "58") (name "unconnected-(U1-NC-Pad17)") (class "Default")
      (node (ref "U1") (pin "17") (pinfunction "NC_17") (pintype "unspecified"))
    )
    (net (code "59") (name "unconnected-(U1-RESV-Pad19)") (class "Default")
      (node (ref "U1") (pin "19") (pinfunction "RESV_19") (pintype "unspecified"))
    )
    (net (code "60") (name "unconnected-(U4-SBU1-PadA8)") (class "Default")
      (node (ref "U4") (pin "A8") (pinfunction "SBU1_A8") (pintype "input+no_connect"))
    )
    (net (code "61") (name "unconnected-(U4-SBU2-PadB8)") (class "Default")
      (node (ref "U4") (pin "B8") (pinfunction "SBU2_B8") (pintype "input+no_connect"))
    )
    (net (code "62") (name "unconnected-(U20-SPICLK-Pad22)") (class "Default")
      (node (ref "U20") (pin "22") (pinfunction "SPICLK_22") (pintype "input+no_connect"))
    )
    (net (code "63") (name "unconnected-(U20-SPICS0-Pad21)") (class "Default")
      (node (ref "U20") (pin "21") (pinfunction "SPICS0_21") (pintype "input+no_connect"))
    )
    (net (code "64") (name "unconnected-(U20-SPID-Pad23)") (class "Default")
      (node (ref "U20") (pin "23") (pinfunction "SPID_23") (pintype "input+no_connect"))
    )
    (net (code "65") (name "unconnected-(U20-SPIHD-Pad19)") (class "Default")
      (node (ref "U20") (pin "19") (pinfunction "SPIHD_19") (pintype "input+no_connect"))
    )
    (net (code "66") (name "unconnected-(U20-SPIQ-Pad24)") (class "Default")
      (node (ref "U20") (pin "24") (pinfunction "SPIQ_24") (pintype "input+no_connect"))
    )
    (net (code "67") (name "unconnected-(U20-SPIWP-Pad20)") (class "Default")
      (node (ref "U20") (pin "20") (pinfunction "SPIWP_20") (pintype "input+no_connect"))
    )
    (net (code "68") (name "unconnected-(U22-ANT-Pad2)") (class "Default")
      (node (ref "U22") (pin "2") (pinfunction "ANT_2") (pintype "unspecified+no_connect"))
    )
  )
)
